# Display.net
KiCad netlist of a schematic drawn in Altium Designer
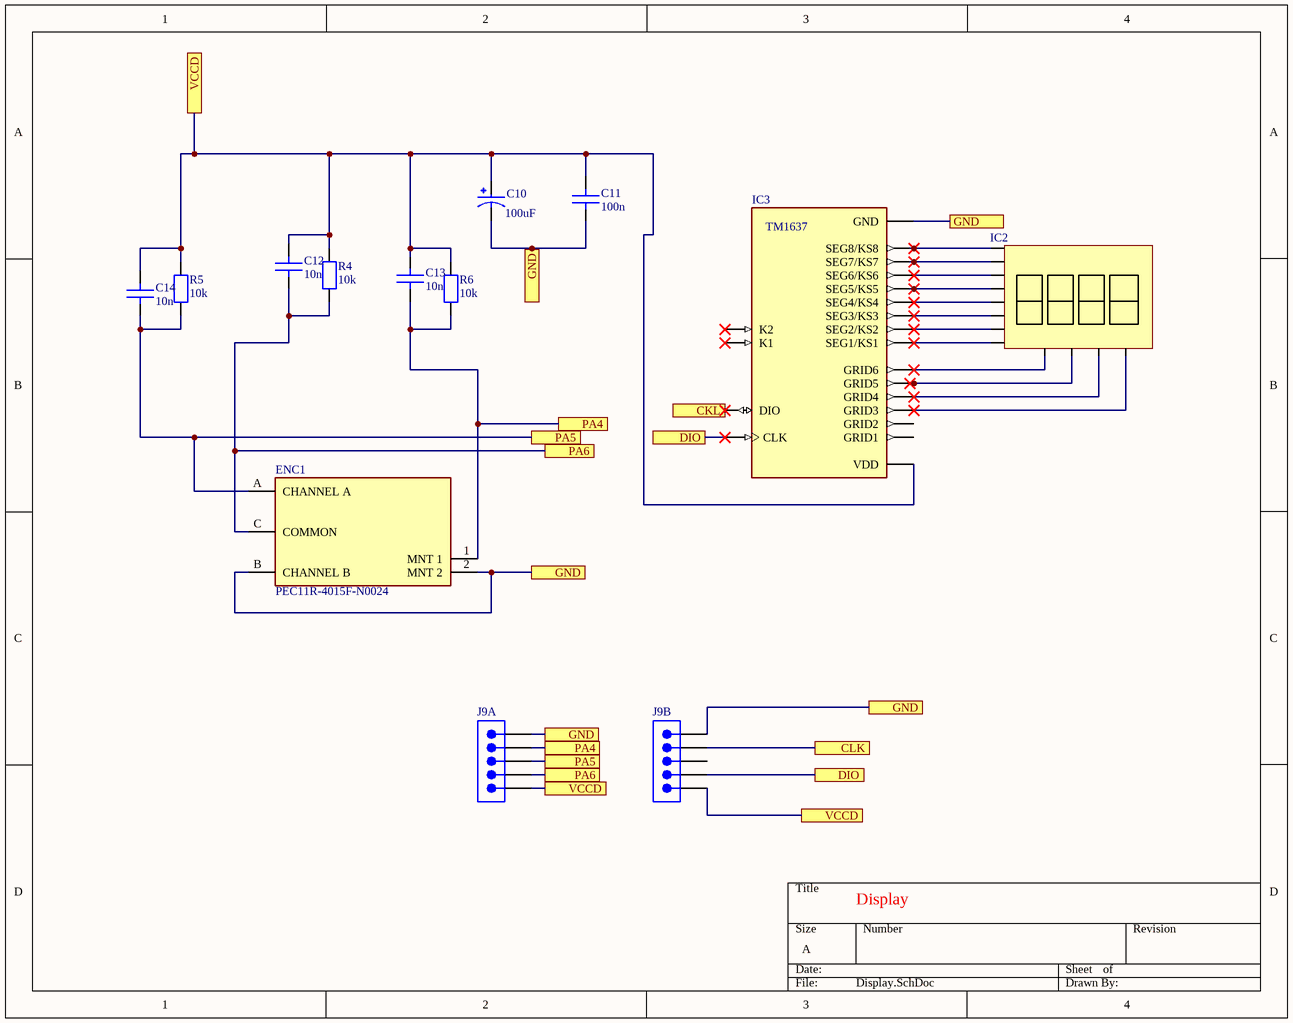
[diagram p0: Display.SchDoc]

(export (version "E")
  (design (tool "Eeschema 10.0.6"))
  (components
    (comp (ref "C10")
      (value "100uF")
      (footprint "CAPPRD350W60D800H1150")
      (description "Capacitor 100 μF, 50 V, steek 3,5 mm, 8x11 mm, generic.")
      (libsource (lib "myOwnLib") (part "Capacitor"))
    )
    (comp (ref "C11")
      (value "100n")
      (footprint "CAP_0805")
      (description "Capacitor SMD 0805 generic.")
      (libsource (lib "myOwnLib") (part "CAP_0805"))
    )
    (comp (ref "C12")
      (value "10n")
      (footprint "CAP_0805")
      (description "Capacitor SMD 0805 generic.")
      (libsource (lib "myOwnLib") (part "CAP_0805"))
    )
    (comp (ref "C13")
      (value "10n")
      (footprint "CAP_0805")
      (description "Capacitor SMD 0805 generic.")
      (libsource (lib "myOwnLib") (part "CAP_0805"))
    )
    (comp (ref "C14")
      (value "10n")
      (footprint "CAP_0805")
      (description "Capacitor SMD 0805 generic.")
      (libsource (lib "myOwnLib") (part "CAP_0805"))
    )
    (comp (ref "ENC1")
      (value "PEC11R-4015F-N0024")
      (footprint "FP-PEC11R-4015F-N0024-MFG")
      (description "ROTARY ENCODER MECHANICAL 24PPR")
      (fields
        (field (name "MANUFACTURER") "Bourns")
        (field (name "OCTOPART") "https://octopart.com/pec11r-4015f-n0024-bourns-26648251")
      )
      (libsource (lib "Altium Content Vault") (part "714335eeadb64c170d88fa1cfc7421d"))
    )
    (comp (ref "IC2")
      (value "KW4-801AVB")
      (footprint "LTC46454G")
      (description "SEVEN_SEG Diplay 4digits")
      (libsource (lib "myOwnLib") (part "KW4-801AVB"))
    )
    (comp (ref "IC3")
      (value "TM1637")
      (footprint "DIP778W43P254L2612H431Q20N")
      (libsource (lib "myOwnLib") (part "TM1637"))
    )
    (comp (ref "J9A")
      (value "61300511121")
      (footprint "61300511121")
      (fields (field (name "MANUFACTURER") "Wurth Electronics"))
      (libsource (lib "myOwnLib") (part "61300511121"))
    )
    (comp (ref "J9B")
      (value "61300511121")
      (footprint "61300511121")
      (fields (field (name "MANUFACTURER") "Wurth Electronics"))
      (libsource (lib "myOwnLib") (part "61300511121"))
    )
    (comp (ref "R4")
      (value "10k")
      (footprint "RES_0805")
      (description "SMD size 0805 Generic.")
      (libsource (lib "myOwnLib") (part "RES_0805"))
    )
    (comp (ref "R5")
      (value "10k")
      (footprint "RES_0805")
      (description "SMD size 0805 Generic.")
      (libsource (lib "myOwnLib") (part "RES_0805"))
    )
    (comp (ref "R6")
      (value "10k")
      (footprint "RES_0805")
      (description "SMD size 0805 Generic.")
      (libsource (lib "myOwnLib") (part "RES_0805"))
    )
  )
  (nets
    (net (code "1") (name "/CKL") (class "Default")
      (node (ref "IC3") (pin "17") (pinfunction "DIO_17") (pintype "bidirectional+no_connect"))
    )
    (net (code "2") (name "/CLK") (class "Default")
      (node (ref "J9B") (pin "4") (pinfunction "4_4") (pintype "passive"))
    )
    (net (code "3") (name "/DIO") (class "Default")
      (node (ref "IC3") (pin "18") (pinfunction "CLK_18") (pintype "input"))
      (node (ref "J9B") (pin "2") (pinfunction "2_2") (pintype "passive"))
    )
    (net (code "4") (name "/GND") (class "Default")
      (node (ref "C10") (pin "N") (pinfunction "N_N") (pintype "passive"))
      (node (ref "C11") (pin "1") (pintype "passive"))
      (node (ref "ENC1") (pin "2") (pinfunction "MNT_2_2") (pintype "passive"))
      (node (ref "ENC1") (pin "B") (pinfunction "CHANNEL_B_B") (pintype "passive"))
      (node (ref "IC3") (pin "1") (pinfunction "GND_1") (pintype "power_in"))
      (node (ref "J9A") (pin "5") (pinfunction "5_5") (pintype "passive"))
      (node (ref "J9B") (pin "5") (pinfunction "5_5") (pintype "passive"))
    )
    (net (code "5") (name "/PA4") (class "Default")
      (node (ref "C13") (pin "2") (pintype "passive"))
      (node (ref "ENC1") (pin "1") (pinfunction "MNT_1_1") (pintype "passive"))
      (node (ref "J9A") (pin "4") (pinfunction "4_4") (pintype "passive"))
      (node (ref "R6") (pin "1") (pintype "passive"))
    )
    (net (code "6") (name "/PA5") (class "Default")
      (node (ref "C14") (pin "1") (pintype "passive"))
      (node (ref "ENC1") (pin "A") (pinfunction "CHANNEL_A_A") (pintype "passive"))
      (node (ref "J9A") (pin "3") (pinfunction "3_3") (pintype "passive"))
      (node (ref "R5") (pin "1") (pintype "passive"))
    )
    (net (code "7") (name "/PA6") (class "Default")
      (node (ref "C12") (pin "1") (pintype "passive"))
      (node (ref "ENC1") (pin "C") (pinfunction "COMMON_C") (pintype "passive"))
      (node (ref "J9A") (pin "2") (pinfunction "2_2") (pintype "passive"))
      (node (ref "R4") (pin "2") (pintype "passive"))
    )
    (net (code "8") (name "/VCCD") (class "Default")
      (node (ref "C10") (pin "P") (pinfunction "P_P") (pintype "passive"))
      (node (ref "C11") (pin "2") (pintype "passive"))
      (node (ref "C12") (pin "2") (pintype "passive"))
      (node (ref "C13") (pin "1") (pintype "passive"))
      (node (ref "C14") (pin "2") (pintype "passive"))
      (node (ref "IC3") (pin "16") (pinfunction "VDD_16") (pintype "power_in"))
      (node (ref "J9A") (pin "1") (pinfunction "1_1") (pintype "passive"))
      (node (ref "J9B") (pin "1") (pinfunction "1_1") (pintype "passive"))
      (node (ref "R4") (pin "1") (pintype "passive"))
      (node (ref "R5") (pin "2") (pintype "passive"))
      (node (ref "R6") (pin "2") (pintype "passive"))
    )
    (net (code "9") (name "unconnected-(IC3-GRID1-Pad15)") (class "Default")
      (node (ref "IC3") (pin "15") (pinfunction "GRID1_15") (pintype "output"))
    )
    (net (code "10") (name "unconnected-(IC3-GRID2-Pad14)") (class "Default")
      (node (ref "IC3") (pin "14") (pinfunction "GRID2_14") (pintype "output"))
    )
    (net (code "11") (name "unconnected-(IC3-GRID3-Pad13)") (class "Default")
      (node (ref "IC3") (pin "13") (pinfunction "GRID3_13") (pintype "output+no_connect"))
    )
    (net (code "12") (name "unconnected-(IC3-GRID4-Pad12)") (class "Default")
      (node (ref "IC3") (pin "12") (pinfunction "GRID4_12") (pintype "output+no_connect"))
    )
    (net (code "13") (name "unconnected-(IC3-GRID5-Pad11)") (class "Default")
      (node (ref "IC3") (pin "11") (pinfunction "GRID5_11") (pintype "output+no_connect"))
    )
    (net (code "14") (name "unconnected-(IC3-GRID6-Pad10)") (class "Default")
      (node (ref "IC3") (pin "10") (pinfunction "GRID6_10") (pintype "output+no_connect"))
    )
    (net (code "15") (name "unconnected-(IC3-K1-Pad19)") (class "Default")
      (node (ref "IC3") (pin "19") (pinfunction "K1_19") (pintype "input+no_connect"))
    )
    (net (code "16") (name "unconnected-(IC3-K2-Pad20)") (class "Default")
      (node (ref "IC3") (pin "20") (pinfunction "K2_20") (pintype "input+no_connect"))
    )
    (net (code "17") (name "unconnected-(IC3-SEG1{slash}KS1-Pad2)") (class "Default")
      (node (ref "IC3") (pin "2") (pinfunction "SEG1/KS1_2") (pintype "output+no_connect"))
    )
    (net (code "18") (name "unconnected-(IC3-SEG2{slash}KS2-Pad3)") (class "Default")
      (node (ref "IC3") (pin "3") (pinfunction "SEG2/KS2_3") (pintype "output+no_connect"))
    )
    (net (code "19") (name "unconnected-(IC3-SEG3{slash}KS3-Pad4)") (class "Default")
      (node (ref "IC3") (pin "4") (pinfunction "SEG3/KS3_4") (pintype "output+no_connect"))
    )
    (net (code "20") (name "unconnected-(IC3-SEG4{slash}KS4-Pad5)") (class "Default")
      (node (ref "IC3") (pin "5") (pinfunction "SEG4/KS4_5") (pintype "output+no_connect"))
    )
    (net (code "21") (name "unconnected-(IC3-SEG5{slash}KS5-Pad6)") (class "Default")
      (node (ref "IC3") (pin "6") (pinfunction "SEG5/KS5_6") (pintype "output+no_connect"))
    )
    (net (code "22") (name "unconnected-(IC3-SEG6{slash}KS6-Pad7)") (class "Default")
      (node (ref "IC3") (pin "7") (pinfunction "SEG6/KS6_7") (pintype "output+no_connect"))
    )
    (net (code "23") (name "unconnected-(IC3-SEG7{slash}KS7-Pad8)") (class "Default")
      (node (ref "IC3") (pin "8") (pinfunction "SEG7/KS7_8") (pintype "output+no_connect"))
    )
    (net (code "24") (name "unconnected-(IC3-SEG8{slash}KS8-Pad9)") (class "Default")
      (node (ref "IC3") (pin "9") (pinfunction "SEG8/KS8_9") (pintype "output+no_connect"))
    )
    (net (code "25") (name "unconnected-(J9B-Pad3)") (class "Default")
      (node (ref "J9B") (pin "3") (pinfunction "3_3") (pintype "passive"))
    )
  )
)
